# IOTest.net
KiCad netlist of a schematic drawn in Altium Designer
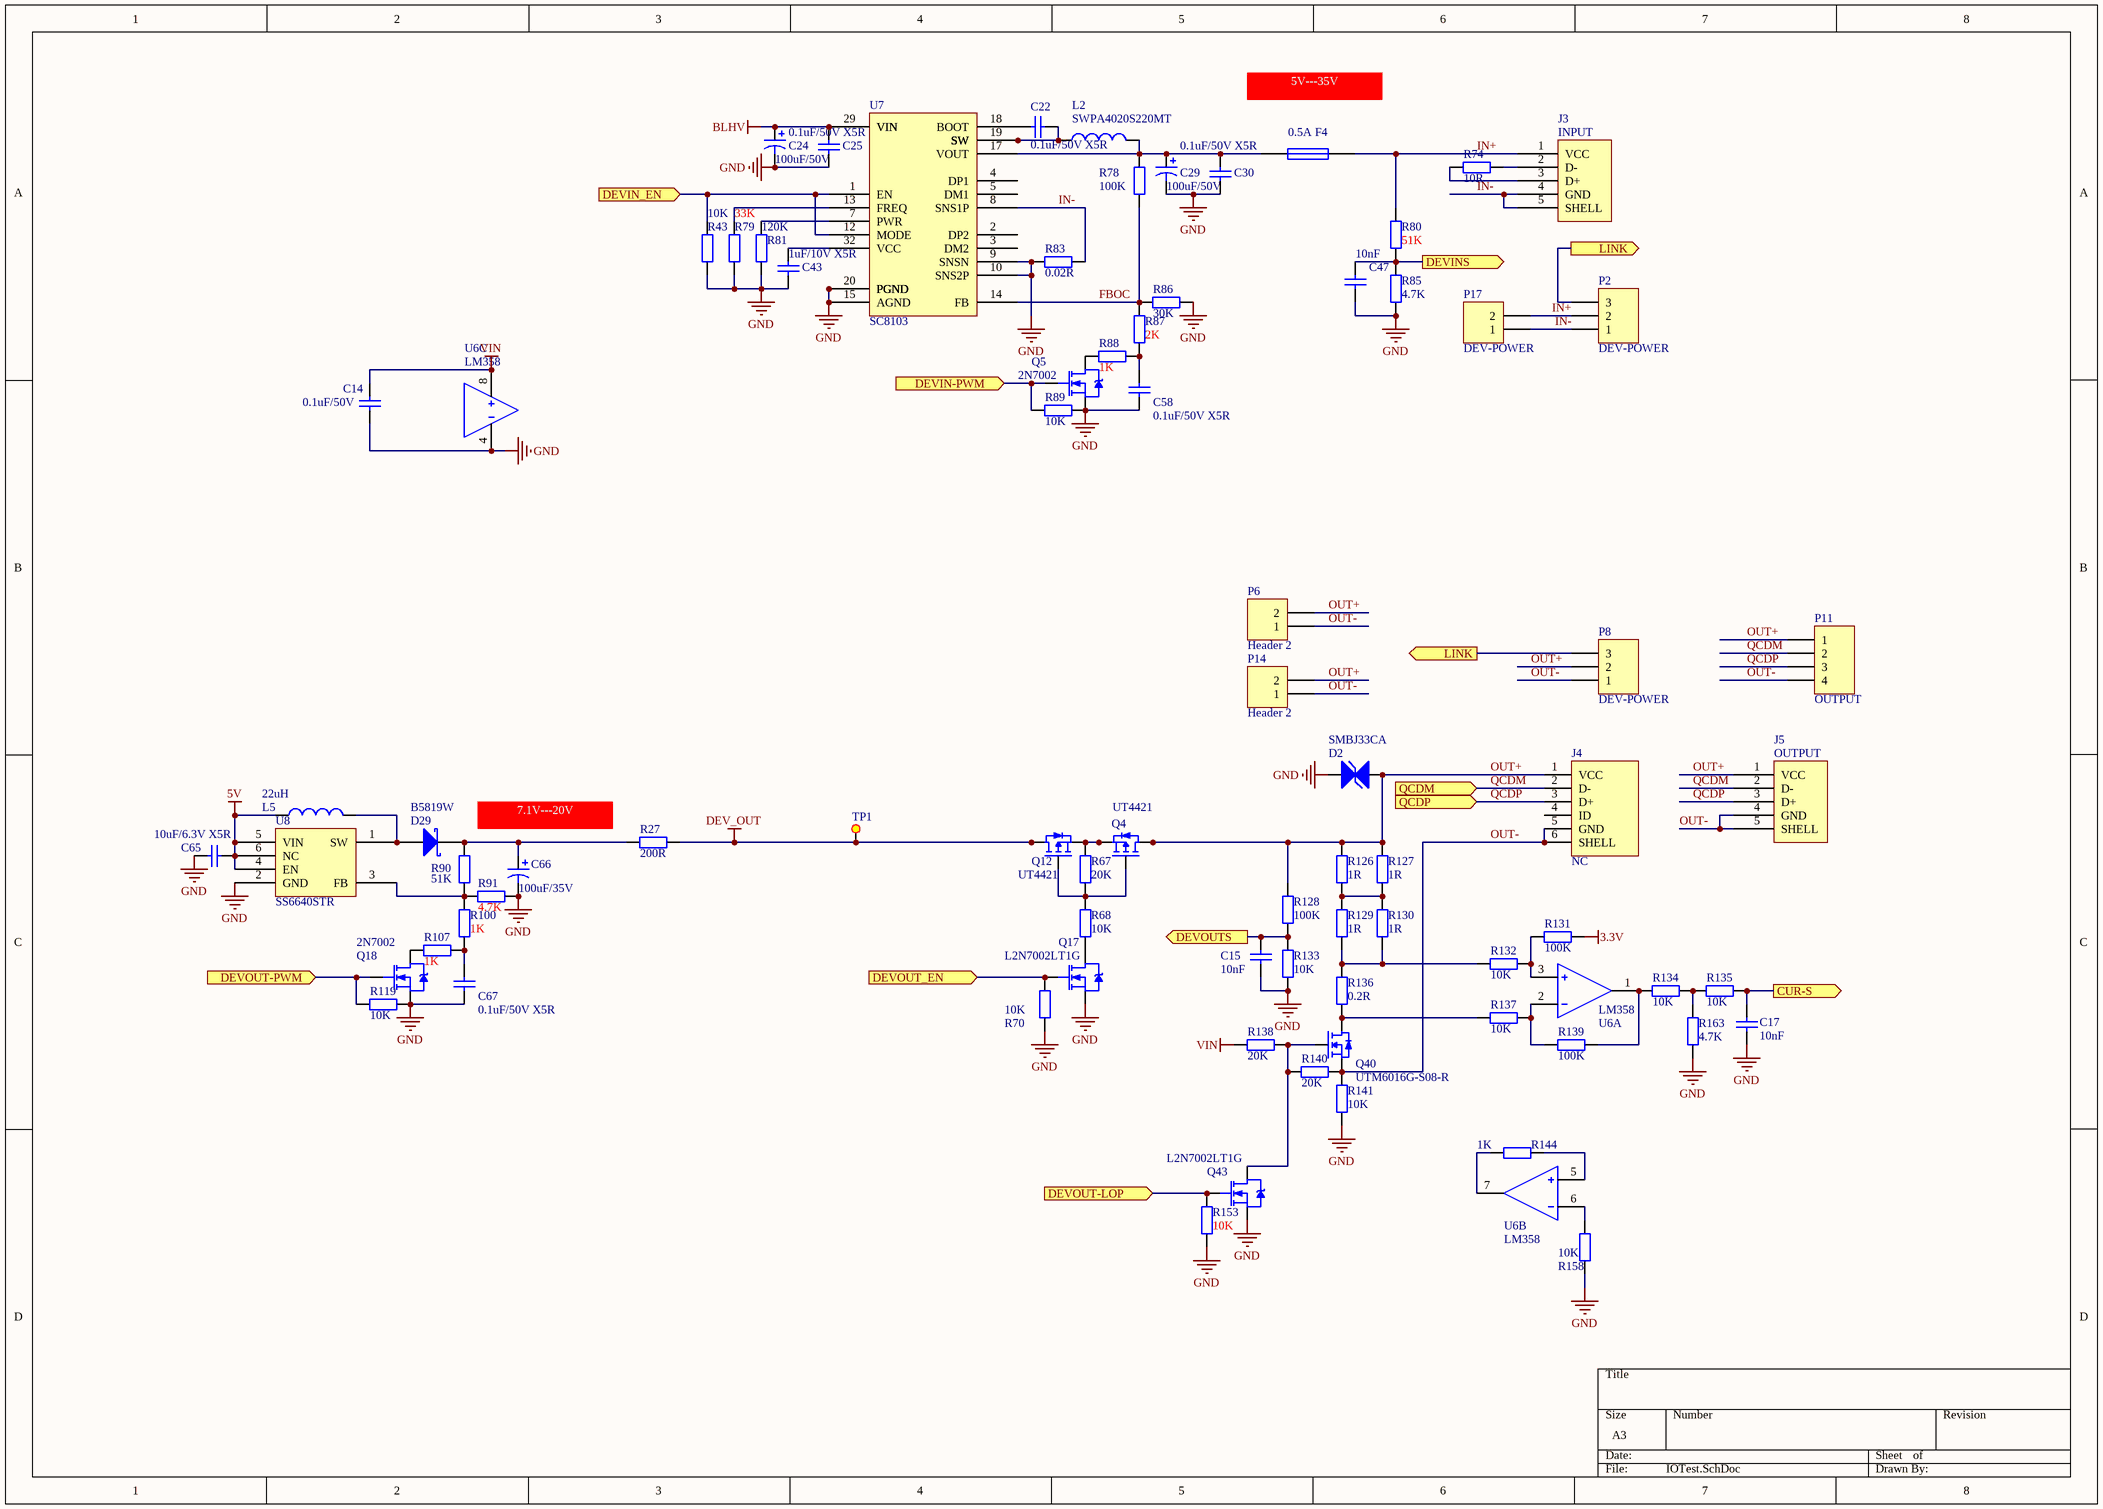
[diagram p0: IOTest.SchDoc]

(export (version "E")
  (design (tool "Eeschema 10.0.6"))
  (components
    (comp (ref "C14")
      (value "0.1uF/50V")
      (footprint "C-0603")
      (description "Capacitor")
      (fields (field (name "PUBLISHER") "Altium Limited"))
      (libsource (lib "Miscellaneous Devices") (part "Cap"))
    )
    (comp (ref "C15")
      (value "10nF")
      (footprint "C-0603")
      (description "Capacitor")
      (fields (field (name "PUBLISHER") "Altium Limited"))
      (libsource (lib "Miscellaneous Devices") (part "Cap"))
    )
    (comp (ref "C17")
      (value "10nF")
      (footprint "C-0603")
      (description "Capacitor")
      (fields (field (name "PUBLISHER") "Altium Limited"))
      (libsource (lib "Miscellaneous Devices") (part "Cap"))
    )
    (comp (ref "C22")
      (value "0.1uF/50V X5R")
      (footprint "C-0603")
      (description "Capacitor")
      (fields (field (name "PUBLISHER") "Altium Limited"))
      (libsource (lib "Miscellaneous Devices") (part "Cap"))
    )
    (comp (ref "C24")
      (value "100uF/50V")
      (footprint "CAPPR-8x12")
      (description "Polarized Capacitor (Radial)")
      (fields (field (name "PUBLISHER") "Altium Limited"))
      (libsource (lib "Miscellaneous Devices") (part "Cap Pol1"))
    )
    (comp (ref "C25")
      (value "0.1uF/50V X5R")
      (footprint "C-0603")
      (description "Capacitor")
      (fields (field (name "PUBLISHER") "Altium Limited"))
      (libsource (lib "Miscellaneous Devices") (part "Cap"))
    )
    (comp (ref "C29")
      (value "100uF/50V")
      (footprint "CAPPR-8x12")
      (description "Polarized Capacitor (Radial)")
      (fields (field (name "PUBLISHER") "Altium Limited"))
      (libsource (lib "Miscellaneous Devices") (part "Cap Pol1"))
    )
    (comp (ref "C30")
      (value "0.1uF/50V X5R")
      (footprint "C-0603")
      (description "Capacitor")
      (fields (field (name "PUBLISHER") "Altium Limited"))
      (libsource (lib "Miscellaneous Devices") (part "Cap"))
    )
    (comp (ref "C43")
      (value "1uF/10V X5R")
      (footprint "C-0603")
      (description "Capacitor")
      (fields (field (name "PUBLISHER") "Altium Limited"))
      (libsource (lib "Miscellaneous Devices") (part "Cap"))
    )
    (comp (ref "C47")
      (value "10nF")
      (footprint "C-0603")
      (description "Capacitor")
      (fields (field (name "PUBLISHER") "Altium Limited"))
      (libsource (lib "Miscellaneous Devices") (part "Cap"))
    )
    (comp (ref "C58")
      (value "0.1uF/50V X5R")
      (footprint "C-0603")
      (description "Capacitor")
      (fields (field (name "PUBLISHER") "Altium Limited"))
      (libsource (lib "Miscellaneous Devices") (part "Cap"))
    )
    (comp (ref "C65")
      (value "10uF/6.3V X5R")
      (footprint "C-0603")
      (description "Capacitor")
      (fields (field (name "PUBLISHER") "Altium Limited"))
      (libsource (lib "Miscellaneous Devices") (part "Cap"))
    )
    (comp (ref "C66")
      (value "100uF/35V")
      (footprint "ToboxStd:CAP-SMD-6.3x7.7")
      (description "Polarized Capacitor (Radial)")
      (fields (field (name "PUBLISHER") "Altium Limited"))
      (libsource (lib "Miscellaneous Devices") (part "Cap Pol1"))
    )
    (comp (ref "C67")
      (value "0.1uF/50V X5R")
      (footprint "C-0603")
      (description "Capacitor")
      (fields (field (name "PUBLISHER") "Altium Limited"))
      (libsource (lib "Miscellaneous Devices") (part "Cap"))
    )
    (comp (ref "D2") (value "SMBJ33CA") (footprint "SMBJ") (libsource (lib "ToboxStd") (part "TVS-D")))
    (comp (ref "D29")
      (value "B5819W")
      (footprint "SOD-123FL")
      (description "Schottky Diode")
      (fields (field (name "PUBLISHER") "Altium Limited"))
      (libsource (lib "Miscellaneous Devices") (part "D Schottky"))
    )
    (comp (ref "F4")
      (value "0.5A")
      (footprint "R-1206")
      (description "Fuse")
      (fields (field (name "PUBLISHER") "Altium Limited"))
      (libsource (lib "Miscellaneous Devices") (part "Fuse 1"))
    )
    (comp (ref "J3")
      (value "INPUT")
      (footprint "ToboxStd:ST-001-15A-1.0")
      (description "USB CONNECTOR")
      (libsource (lib "Tobox") (part "USB-CON"))
    )
    (comp (ref "J4")
      (value "NC")
      (footprint "ST-MICROUSB-03A")
      (description "MICRO-USB-B")
      (libsource (lib "ToboxStd") (part "MICRO-USB-B"))
    )
    (comp (ref "J5")
      (value "OUTPUT")
      (footprint "ToboxStd:ST-001-15A-1.0")
      (description "USB CONNECTOR")
      (libsource (lib "Tobox") (part "USB-CON"))
    )
    (comp (ref "L2")
      (value "SWPA4020S220MT")
      (footprint "SWPA4020S")
      (description "Inductor")
      (fields (field (name "PUBLISHER") "Altium Limited"))
      (libsource (lib "Miscellaneous Devices") (part "Inductor"))
    )
    (comp (ref "L5")
      (value "22uH")
      (footprint "DG3521")
      (description "Inductor")
      (fields (field (name "PUBLISHER") "Altium Limited"))
      (libsource (lib "Miscellaneous Devices") (part "Inductor"))
    )
    (comp (ref "P2")
      (value "DEV-POWER")
      (footprint "XH 2.54-3P")
      (description "Header, 3-Pin")
      (fields (field (name "PUBLISHER") "Altium Limited"))
      (libsource (lib "Miscellaneous Connectors") (part "Header 3"))
    )
    (comp (ref "P6")
      (value "Header 2")
      (footprint "XH 2.54-2P")
      (description "Header, 2-Pin")
      (fields (field (name "PUBLISHER") "Altium Limited"))
      (libsource (lib "Miscellaneous Connectors") (part "Header 2"))
    )
    (comp (ref "P8")
      (value "DEV-POWER")
      (footprint "XH 2.54-3P")
      (description "Header, 3-Pin")
      (fields (field (name "PUBLISHER") "Altium Limited"))
      (libsource (lib "Miscellaneous Connectors") (part "Header 3"))
    )
    (comp (ref "P11")
      (value "OUTPUT")
      (footprint "XH 2.54-4P")
      (description "Header, 4-Pin")
      (fields (field (name "PUBLISHER") "Altium Limited"))
      (libsource (lib "Miscellaneous Connectors") (part "Header 4"))
    )
    (comp (ref "P14")
      (value "Header 2")
      (footprint "XH 2.54-2P")
      (description "Header, 2-Pin")
      (fields (field (name "PUBLISHER") "Altium Limited"))
      (libsource (lib "Miscellaneous Connectors") (part "Header 2"))
    )
    (comp (ref "P17")
      (value "DEV-POWER")
      (footprint "XH 2.54-2P")
      (description "Header, 2-Pin")
      (fields (field (name "PUBLISHER") "Altium Limited"))
      (libsource (lib "Miscellaneous Connectors") (part "Header 2"))
    )
    (comp (ref "Q4")
      (value "UT4421")
      (footprint "SOIC8")
      (description "SO8-PMOS")
      (libsource (lib "Tobox") (part "SO8-PMOS"))
    )
    (comp (ref "Q5")
      (value "2N7002")
      (footprint "SOT23-3")
      (description "N-Channel Power MOSFET")
      (fields (field (name "PUBLISHER") "Altium Limited"))
      (libsource (lib "Miscellaneous Devices") (part "NMOS-2"))
    )
    (comp (ref "Q12")
      (value "UT4421")
      (footprint "SOIC8")
      (description "SO8-PMOS")
      (libsource (lib "Tobox") (part "SO8-PMOS"))
    )
    (comp (ref "Q17")
      (value "L2N7002LT1G")
      (footprint "SOT23-3")
      (description "N-Channel Power MOSFET")
      (fields (field (name "PUBLISHER") "Altium Limited"))
      (libsource (lib "Miscellaneous Devices") (part "NMOS-2"))
    )
    (comp (ref "Q18")
      (value "2N7002")
      (footprint "SOT23-3")
      (description "N-Channel Power MOSFET")
      (fields (field (name "PUBLISHER") "Altium Limited"))
      (libsource (lib "Miscellaneous Devices") (part "NMOS-2"))
    )
    (comp (ref "Q40")
      (value "UTM6016G-S08-R")
      (footprint "SOIC8")
      (description "SO8-NMOS")
      (libsource (lib "Tobox") (part "SO8-NMOS"))
    )
    (comp (ref "Q43")
      (value "L2N7002LT1G")
      (footprint "SOT23-3")
      (description "N-Channel Power MOSFET")
      (fields (field (name "PUBLISHER") "Altium Limited"))
      (libsource (lib "Miscellaneous Devices") (part "NMOS-2"))
    )
    (comp (ref "R27")
      (value "200R")
      (footprint "R-0805")
      (description "Resistor")
      (fields (field (name "PUBLISHER") "Altium Limited"))
      (libsource (lib "Miscellaneous Devices") (part "Res2"))
    )
    (comp (ref "R43")
      (value "10K")
      (footprint "R-0603")
      (description "Resistor")
      (fields (field (name "PUBLISHER") "Altium Limited"))
      (libsource (lib "") (part "Res2_2"))
    )
    (comp (ref "R67")
      (value "20K")
      (footprint "R-0603")
      (description "Resistor")
      (fields (field (name "PUBLISHER") "Altium Limited"))
      (libsource (lib "Miscellaneous Devices") (part "Res2"))
    )
    (comp (ref "R68")
      (value "10K")
      (footprint "R-0603")
      (description "Resistor")
      (fields (field (name "PUBLISHER") "Altium Limited"))
      (libsource (lib "Miscellaneous Devices") (part "Res2"))
    )
    (comp (ref "R70")
      (value "10K")
      (footprint "R-0603")
      (description "Resistor")
      (fields (field (name "PUBLISHER") "Altium Limited"))
      (libsource (lib "") (part "Res2_2"))
    )
    (comp (ref "R74")
      (value "10R")
      (footprint "R-0603")
      (description "Resistor")
      (fields (field (name "PUBLISHER") "Altium Limited"))
      (libsource (lib "") (part "Res2_3"))
    )
    (comp (ref "R78")
      (value "100K")
      (footprint "R-0603")
      (description "Resistor")
      (fields (field (name "PUBLISHER") "Altium Limited"))
      (libsource (lib "") (part "Res2_3"))
    )
    (comp (ref "R79")
      (value "33K")
      (footprint "R-0603")
      (description "Resistor")
      (fields (field (name "PUBLISHER") "Altium Limited"))
      (libsource (lib "") (part "Res2_2"))
    )
    (comp (ref "R80")
      (value "51K")
      (footprint "R-0603")
      (description "Resistor")
      (fields (field (name "PUBLISHER") "Altium Limited"))
      (libsource (lib "Miscellaneous Devices") (part "Res2"))
    )
    (comp (ref "R81")
      (value "120K")
      (footprint "R-0603")
      (description "Resistor")
      (fields (field (name "PUBLISHER") "Altium Limited"))
      (libsource (lib "") (part "Res2_2"))
    )
    (comp (ref "R83")
      (value "0.02R")
      (footprint "R-2010")
      (description "Resistor")
      (fields (field (name "PUBLISHER") "Altium Limited"))
      (libsource (lib "Miscellaneous Devices") (part "Res2"))
    )
    (comp (ref "R85")
      (value "4.7K")
      (footprint "R-0603")
      (description "Resistor")
      (fields (field (name "PUBLISHER") "Altium Limited"))
      (libsource (lib "Miscellaneous Devices") (part "Res2"))
    )
    (comp (ref "R86")
      (value "30K")
      (footprint "R-0603")
      (description "Resistor")
      (fields (field (name "PUBLISHER") "Altium Limited"))
      (libsource (lib "") (part "Res2_1"))
    )
    (comp (ref "R87")
      (value "2K")
      (footprint "R-0603")
      (description "Resistor")
      (fields (field (name "PUBLISHER") "Altium Limited"))
      (libsource (lib "") (part "Res2_2"))
    )
    (comp (ref "R88")
      (value "1K")
      (footprint "R-0603")
      (description "Resistor")
      (fields (field (name "PUBLISHER") "Altium Limited"))
      (libsource (lib "") (part "Res2_1"))
    )
    (comp (ref "R89")
      (value "10K")
      (footprint "R-0603")
      (description "Resistor")
      (fields (field (name "PUBLISHER") "Altium Limited"))
      (libsource (lib "") (part "Res2_1"))
    )
    (comp (ref "R90")
      (value "51K")
      (footprint "R-0603")
      (description "Resistor")
      (fields (field (name "PUBLISHER") "Altium Limited"))
      (libsource (lib "") (part "Res2_1"))
    )
    (comp (ref "R91")
      (value "4.7K")
      (footprint "R-0603")
      (description "Resistor")
      (fields (field (name "PUBLISHER") "Altium Limited"))
      (libsource (lib "") (part "Res2_2"))
    )
    (comp (ref "R100")
      (value "1K")
      (footprint "R-0603")
      (description "Resistor")
      (fields (field (name "PUBLISHER") "Altium Limited"))
      (libsource (lib "") (part "Res2_2"))
    )
    (comp (ref "R107")
      (value "1K")
      (footprint "R-0603")
      (description "Resistor")
      (fields (field (name "PUBLISHER") "Altium Limited"))
      (libsource (lib "") (part "Res2_1"))
    )
    (comp (ref "R119")
      (value "10K")
      (footprint "R-0603")
      (description "Resistor")
      (fields (field (name "PUBLISHER") "Altium Limited"))
      (libsource (lib "") (part "Res2_1"))
    )
    (comp (ref "R126")
      (value "1R")
      (footprint "ToboxStd:R-2512")
      (description "Resistor")
      (fields (field (name "PUBLISHER") "Altium Limited"))
      (libsource (lib "") (part "Res2_1"))
    )
    (comp (ref "R127")
      (value "1R")
      (footprint "ToboxStd:R-2512")
      (description "Resistor")
      (fields (field (name "PUBLISHER") "Altium Limited"))
      (libsource (lib "") (part "Res2_2"))
    )
    (comp (ref "R128")
      (value "100K")
      (footprint "R-0603")
      (description "Resistor")
      (fields (field (name "PUBLISHER") "Altium Limited"))
      (libsource (lib "") (part "Res2_2"))
    )
    (comp (ref "R129")
      (value "1R")
      (footprint "ToboxStd:R-2512")
      (description "Resistor")
      (fields (field (name "PUBLISHER") "Altium Limited"))
      (libsource (lib "") (part "Res2_2"))
    )
    (comp (ref "R130")
      (value "1R")
      (footprint "ToboxStd:R-2512")
      (description "Resistor")
      (fields (field (name "PUBLISHER") "Altium Limited"))
      (libsource (lib "") (part "Res2_3"))
    )
    (comp (ref "R131")
      (value "100K")
      (footprint "R-0603")
      (description "Resistor")
      (fields (field (name "PUBLISHER") "Altium Limited"))
      (libsource (lib "Miscellaneous Devices") (part "Res2"))
    )
    (comp (ref "R132")
      (value "10K")
      (footprint "R-0603")
      (description "Resistor")
      (fields (field (name "PUBLISHER") "Altium Limited"))
      (libsource (lib "Miscellaneous Devices") (part "Res2"))
    )
    (comp (ref "R133")
      (value "10K")
      (footprint "R-0603")
      (description "Resistor")
      (fields (field (name "PUBLISHER") "Altium Limited"))
      (libsource (lib "") (part "Res2_2"))
    )
    (comp (ref "R134")
      (value "10K")
      (footprint "R-0603")
      (description "Resistor")
      (fields (field (name "PUBLISHER") "Altium Limited"))
      (libsource (lib "Miscellaneous Devices") (part "Res2"))
    )
    (comp (ref "R135")
      (value "10K")
      (footprint "R-0603")
      (description "Resistor")
      (fields (field (name "PUBLISHER") "Altium Limited"))
      (libsource (lib "Miscellaneous Devices") (part "Res2"))
    )
    (comp (ref "R136")
      (value "0.2R")
      (footprint "R-2512HP")
      (description "Resistor")
      (fields (field (name "PUBLISHER") "Altium Limited"))
      (libsource (lib "") (part "Res2_2"))
    )
    (comp (ref "R137")
      (value "10K")
      (footprint "R-0603")
      (description "Resistor")
      (fields (field (name "PUBLISHER") "Altium Limited"))
      (libsource (lib "Miscellaneous Devices") (part "Res2"))
    )
    (comp (ref "R138")
      (value "20K")
      (footprint "R-0603")
      (description "Resistor")
      (fields (field (name "PUBLISHER") "Altium Limited"))
      (libsource (lib "Miscellaneous Devices") (part "Res2"))
    )
    (comp (ref "R139")
      (value "100K")
      (footprint "R-0603")
      (description "Resistor")
      (fields (field (name "PUBLISHER") "Altium Limited"))
      (libsource (lib "Miscellaneous Devices") (part "Res2"))
    )
    (comp (ref "R140")
      (value "20K")
      (footprint "R-0603")
      (description "Resistor")
      (fields (field (name "PUBLISHER") "Altium Limited"))
      (libsource (lib "Miscellaneous Devices") (part "Res2"))
    )
    (comp (ref "R141")
      (value "10K")
      (footprint "R-0603")
      (description "Resistor")
      (fields (field (name "PUBLISHER") "Altium Limited"))
      (libsource (lib "") (part "Res2_3"))
    )
    (comp (ref "R144")
      (value "1K")
      (footprint "R-0603")
      (description "Resistor")
      (fields (field (name "PUBLISHER") "Altium Limited"))
      (libsource (lib "") (part "Res2_3"))
    )
    (comp (ref "R153")
      (value "10K")
      (footprint "R-0603")
      (description "Resistor")
      (fields (field (name "PUBLISHER") "Altium Limited"))
      (libsource (lib "") (part "Res2_3"))
    )
    (comp (ref "R158")
      (value "10K")
      (footprint "R-0603")
      (description "Resistor")
      (fields (field (name "PUBLISHER") "Altium Limited"))
      (libsource (lib "") (part "Res2_1"))
    )
    (comp (ref "R163")
      (value "4.7K")
      (footprint "R-0603")
      (description "Resistor")
      (fields (field (name "PUBLISHER") "Altium Limited"))
      (libsource (lib "") (part "Res2_2"))
    )
    (comp (ref "TP1") (value "~") (footprint "TestPoint-1.5mm") (libsource (lib "Tobox") (part "TEST_P")))
    (comp (ref "U6") (value "LM358") (footprint "SOIC8") (libsource (lib "Tobox") (part "Dual_OPAMP")))
    (comp (ref "U7") (value "SC8103") (footprint "SC8103") (libsource (lib "ToboxStd") (part "SC8103")))
    (comp (ref "U8")
      (value "SS6640STR")
      (footprint "SOT23-6")
      (description "AX5523")
      (libsource (lib "ToboxStd") (part "AX5523"))
    )
  )
  (nets
    (net (code "1") (name "/CUR-S") (class "Default")
      (node (ref "C17") (pin "2") (pinfunction "2_2") (pintype "passive"))
      (node (ref "R135") (pin "2") (pinfunction "2_2") (pintype "passive"))
    )
    (net (code "2") (name "/DEVIN-PWM") (class "Default")
      (node (ref "Q5") (pin "1") (pinfunction "G_1") (pintype "passive"))
      (node (ref "R89") (pin "2") (pinfunction "2_2") (pintype "passive"))
    )
    (net (code "3") (name "/DEVINS") (class "Default")
      (node (ref "C47") (pin "2") (pinfunction "2_2") (pintype "passive"))
      (node (ref "R80") (pin "1") (pinfunction "1_1") (pintype "passive"))
      (node (ref "R85") (pin "2") (pinfunction "2_2") (pintype "passive"))
    )
    (net (code "4") (name "/DEVIN_EN") (class "Default")
      (node (ref "R43") (pin "2") (pinfunction "2_2") (pintype "passive"))
      (node (ref "U7") (pin "1") (pinfunction "EN_1") (pintype "passive"))
      (node (ref "U7") (pin "12") (pinfunction "MODE_12") (pintype "passive"))
    )
    (net (code "5") (name "/DEVOUT-LOP") (class "Default")
      (node (ref "Q43") (pin "1") (pinfunction "G_1") (pintype "passive"))
      (node (ref "R153") (pin "1") (pinfunction "1_1") (pintype "passive"))
    )
    (net (code "6") (name "/DEVOUT-PWM") (class "Default")
      (node (ref "Q18") (pin "1") (pinfunction "G_1") (pintype "passive"))
      (node (ref "R119") (pin "2") (pinfunction "2_2") (pintype "passive"))
    )
    (net (code "7") (name "/DEVOUTS") (class "Default")
      (node (ref "C15") (pin "2") (pinfunction "2_2") (pintype "passive"))
      (node (ref "R128") (pin "1") (pinfunction "1_1") (pintype "passive"))
      (node (ref "R133") (pin "2") (pinfunction "2_2") (pintype "passive"))
    )
    (net (code "8") (name "/DEVOUT_EN") (class "Default")
      (node (ref "Q17") (pin "1") (pinfunction "G_1") (pintype "passive"))
      (node (ref "R70") (pin "2") (pinfunction "2_2") (pintype "passive"))
    )
    (net (code "9") (name "/FBOC") (class "Default")
      (node (ref "R78") (pin "2") (pinfunction "2_2") (pintype "passive"))
      (node (ref "R86") (pin "2") (pinfunction "2_2") (pintype "passive"))
      (node (ref "R87") (pin "2") (pinfunction "2_2") (pintype "passive"))
      (node (ref "U7") (pin "14") (pinfunction "FB_14") (pintype "passive"))
    )
    (net (code "10") (name "/IN+") (class "Default")
      (node (ref "F4") (pin "2") (pinfunction "2_2") (pintype "passive"))
      (node (ref "J3") (pin "1") (pinfunction "VCC_1") (pintype "passive"))
      (node (ref "P17") (pin "2") (pinfunction "2_2") (pintype "passive"))
      (node (ref "P2") (pin "2") (pinfunction "2_2") (pintype "passive"))
      (node (ref "R80") (pin "2") (pinfunction "2_2") (pintype "passive"))
    )
    (net (code "11") (name "/IN-") (class "Default")
      (node (ref "J3") (pin "4") (pinfunction "GND_4") (pintype "passive"))
      (node (ref "J3") (pin "5") (pinfunction "SHELL_5") (pintype "passive"))
      (node (ref "P17") (pin "1") (pinfunction "1_1") (pintype "passive"))
      (node (ref "P2") (pin "1") (pinfunction "1_1") (pintype "passive"))
      (node (ref "R83") (pin "2") (pinfunction "2_2") (pintype "passive"))
      (node (ref "U7") (pin "8") (pinfunction "SNS1P_8") (pintype "passive"))
    )
    (net (code "12") (name "/LINK") (class "Default")
      (node (ref "P2") (pin "3") (pinfunction "3_3") (pintype "passive"))
      (node (ref "P8") (pin "3") (pinfunction "3_3") (pintype "passive"))
    )
    (net (code "13") (name "/OUT+") (class "Default")
      (node (ref "D2") (pin "2") (pinfunction "2_2") (pintype "passive"))
      (node (ref "J4") (pin "1") (pinfunction "VCC_1") (pintype "passive"))
      (node (ref "J5") (pin "1") (pinfunction "VCC_1") (pintype "passive"))
      (node (ref "P11") (pin "1") (pinfunction "1_1") (pintype "passive"))
      (node (ref "P14") (pin "2") (pinfunction "2_2") (pintype "passive"))
      (node (ref "P6") (pin "2") (pinfunction "2_2") (pintype "passive"))
      (node (ref "P8") (pin "2") (pinfunction "2_2") (pintype "passive"))
      (node (ref "Q4") (pin "5") (pinfunction "D_5") (pintype "passive"))
      (node (ref "Q4") (pin "6") (pinfunction "D_6") (pintype "passive"))
      (node (ref "Q4") (pin "7") (pinfunction "D_7") (pintype "passive"))
      (node (ref "Q4") (pin "8") (pinfunction "D_8") (pintype "passive"))
      (node (ref "R126") (pin "1") (pinfunction "1_1") (pintype "passive"))
      (node (ref "R127") (pin "2") (pinfunction "2_2") (pintype "passive"))
      (node (ref "R128") (pin "2") (pinfunction "2_2") (pintype "passive"))
    )
    (net (code "14") (name "/OUT-") (class "Default")
      (node (ref "J4") (pin "5") (pinfunction "GND_5") (pintype "passive"))
      (node (ref "J4") (pin "6") (pinfunction "SHELL_6") (pintype "passive"))
      (node (ref "J5") (pin "4") (pinfunction "GND_4") (pintype "passive"))
      (node (ref "J5") (pin "5") (pinfunction "SHELL_5") (pintype "passive"))
      (node (ref "P11") (pin "4") (pinfunction "4_4") (pintype "passive"))
      (node (ref "P14") (pin "1") (pinfunction "1_1") (pintype "passive"))
      (node (ref "P6") (pin "1") (pinfunction "1_1") (pintype "passive"))
      (node (ref "P8") (pin "1") (pinfunction "1_1") (pintype "passive"))
      (node (ref "Q40") (pin "1") (pinfunction "S_1") (pintype "passive"))
      (node (ref "Q40") (pin "2") (pinfunction "S_2") (pintype "passive"))
      (node (ref "Q40") (pin "3") (pinfunction "S_3") (pintype "passive"))
      (node (ref "R140") (pin "2") (pinfunction "2_2") (pintype "passive"))
      (node (ref "R141") (pin "1") (pinfunction "1_1") (pintype "passive"))
    )
    (net (code "15") (name "/QCDM") (class "Default")
      (node (ref "J4") (pin "2") (pinfunction "D-_2") (pintype "passive"))
      (node (ref "J5") (pin "2") (pinfunction "D-_2") (pintype "passive"))
      (node (ref "P11") (pin "2") (pinfunction "2_2") (pintype "passive"))
    )
    (net (code "16") (name "/QCDP") (class "Default")
      (node (ref "J4") (pin "3") (pinfunction "D+_3") (pintype "passive"))
      (node (ref "J5") (pin "3") (pinfunction "D+_3") (pintype "passive"))
      (node (ref "P11") (pin "3") (pinfunction "3_3") (pintype "passive"))
    )
    (net (code "17") (name "3.3V") (class "Default")
      (node (ref "R131") (pin "2") (pinfunction "2_2") (pintype "passive"))
    )
    (net (code "18") (name "5V") (class "Default")
      (node (ref "C65") (pin "2") (pinfunction "2_2") (pintype "passive"))
      (node (ref "L5") (pin "1") (pinfunction "1_1") (pintype "passive"))
      (node (ref "U8") (pin "4") (pinfunction "EN_4") (pintype "passive"))
      (node (ref "U8") (pin "5") (pinfunction "VIN_5") (pintype "passive"))
      (node (ref "U8") (pin "6") (pinfunction "NC_6") (pintype "passive"))
    )
    (net (code "19") (name "BLHV") (class "Default")
      (node (ref "C24") (pin "1") (pinfunction "1_1") (pintype "passive"))
      (node (ref "C25") (pin "2") (pinfunction "2_2") (pintype "passive"))
      (node (ref "U7") (pin "29") (pinfunction "VIN_29") (pintype "passive"))
      (node (ref "U7") (pin "30") (pinfunction "VIN_30") (pintype "passive"))
      (node (ref "U7") (pin "31") (pinfunction "VIN_31") (pintype "passive"))
    )
    (net (code "20") (name "DEV_OUT") (class "Default")
      (node (ref "Q12") (pin "5") (pinfunction "D_5") (pintype "passive"))
      (node (ref "Q12") (pin "6") (pinfunction "D_6") (pintype "passive"))
      (node (ref "Q12") (pin "7") (pinfunction "D_7") (pintype "passive"))
      (node (ref "Q12") (pin "8") (pinfunction "D_8") (pintype "passive"))
      (node (ref "R27") (pin "2") (pinfunction "2_2") (pintype "passive"))
      (node (ref "TP1") (pin "1") (pinfunction "1_1") (pintype "passive"))
    )
    (net (code "21") (name "GND") (class "Default")
      (node (ref "C14") (pin "2") (pinfunction "2_2") (pintype "passive"))
      (node (ref "C15") (pin "1") (pinfunction "1_1") (pintype "passive"))
      (node (ref "C17") (pin "1") (pinfunction "1_1") (pintype "passive"))
      (node (ref "C24") (pin "2") (pinfunction "2_2") (pintype "passive"))
      (node (ref "C25") (pin "1") (pinfunction "1_1") (pintype "passive"))
      (node (ref "C29") (pin "2") (pinfunction "2_2") (pintype "passive"))
      (node (ref "C30") (pin "1") (pinfunction "1_1") (pintype "passive"))
      (node (ref "C43") (pin "1") (pinfunction "1_1") (pintype "passive"))
      (node (ref "C47") (pin "1") (pinfunction "1_1") (pintype "passive"))
      (node (ref "C58") (pin "2") (pinfunction "2_2") (pintype "passive"))
      (node (ref "C65") (pin "1") (pinfunction "1_1") (pintype "passive"))
      (node (ref "C66") (pin "2") (pinfunction "2_2") (pintype "passive"))
      (node (ref "C67") (pin "2") (pinfunction "2_2") (pintype "passive"))
      (node (ref "D2") (pin "1") (pinfunction "1_1") (pintype "passive"))
      (node (ref "Q17") (pin "2") (pinfunction "D_2") (pintype "passive"))
      (node (ref "Q18") (pin "2") (pinfunction "D_2") (pintype "passive"))
      (node (ref "Q43") (pin "2") (pinfunction "D_2") (pintype "passive"))
      (node (ref "Q5") (pin "2") (pinfunction "D_2") (pintype "passive"))
      (node (ref "R119") (pin "1") (pinfunction "1_1") (pintype "passive"))
      (node (ref "R133") (pin "1") (pinfunction "1_1") (pintype "passive"))
      (node (ref "R141") (pin "2") (pinfunction "2_2") (pintype "passive"))
      (node (ref "R153") (pin "2") (pinfunction "2_2") (pintype "passive"))
      (node (ref "R158") (pin "2") (pinfunction "2_2") (pintype "passive"))
      (node (ref "R163") (pin "1") (pinfunction "1_1") (pintype "passive"))
      (node (ref "R43") (pin "1") (pinfunction "1_1") (pintype "passive"))
      (node (ref "R70") (pin "1") (pinfunction "1_1") (pintype "passive"))
      (node (ref "R79") (pin "1") (pinfunction "1_1") (pintype "passive"))
      (node (ref "R81") (pin "1") (pinfunction "1_1") (pintype "passive"))
      (node (ref "R83") (pin "1") (pinfunction "1_1") (pintype "passive"))
      (node (ref "R85") (pin "1") (pinfunction "1_1") (pintype "passive"))
      (node (ref "R86") (pin "1") (pinfunction "1_1") (pintype "passive"))
      (node (ref "R89") (pin "1") (pinfunction "1_1") (pintype "passive"))
      (node (ref "R91") (pin "2") (pinfunction "2_2") (pintype "passive"))
      (node (ref "U6") (pin "4") (pinfunction "4_4") (pintype "passive"))
      (node (ref "U7") (pin "10") (pinfunction "SNS2P_10") (pintype "passive"))
      (node (ref "U7") (pin "15") (pinfunction "AGND_15") (pintype "passive"))
      (node (ref "U7") (pin "20") (pinfunction "PGND_20") (pintype "passive"))
      (node (ref "U7") (pin "21") (pinfunction "PGND_21") (pintype "passive"))
      (node (ref "U7") (pin "22") (pinfunction "PGND_22") (pintype "passive"))
      (node (ref "U7") (pin "23") (pinfunction "PGND_23") (pintype "passive"))
      (node (ref "U7") (pin "24") (pinfunction "PGND_24") (pintype "passive"))
      (node (ref "U7") (pin "9") (pinfunction "SNSN_9") (pintype "passive"))
      (node (ref "U8") (pin "2") (pinfunction "GND_2") (pintype "passive"))
    )
    (net (code "22") (name "Net-(C22-Pad1)") (class "Default")
      (node (ref "C22") (pin "1") (pinfunction "1_1") (pintype "passive"))
      (node (ref "L2") (pin "1") (pinfunction "1_1") (pintype "passive"))
      (node (ref "U7") (pin "16") (pinfunction "SW_16") (pintype "passive"))
      (node (ref "U7") (pin "19") (pinfunction "SW_19") (pintype "passive"))
      (node (ref "U7") (pin "25") (pinfunction "SW_25") (pintype "passive"))
      (node (ref "U7") (pin "26") (pinfunction "SW_26") (pintype "passive"))
      (node (ref "U7") (pin "27") (pinfunction "SW_27") (pintype "passive"))
      (node (ref "U7") (pin "28") (pinfunction "SW_28") (pintype "passive"))
    )
    (net (code "23") (name "Net-(C58-Pad1)") (class "Default")
      (node (ref "C58") (pin "1") (pinfunction "1_1") (pintype "passive"))
      (node (ref "R87") (pin "1") (pinfunction "1_1") (pintype "passive"))
      (node (ref "R88") (pin "1") (pinfunction "1_1") (pintype "passive"))
    )
    (net (code "24") (name "Net-(C67-Pad1)") (class "Default")
      (node (ref "C67") (pin "1") (pinfunction "1_1") (pintype "passive"))
      (node (ref "R100") (pin "1") (pinfunction "1_1") (pintype "passive"))
      (node (ref "R107") (pin "1") (pinfunction "1_1") (pintype "passive"))
    )
    (net (code "25") (name "Net-(D29-A)") (class "Default")
      (node (ref "D29") (pin "1") (pinfunction "A_1") (pintype "passive"))
      (node (ref "L5") (pin "2") (pinfunction "2_2") (pintype "passive"))
      (node (ref "U8") (pin "1") (pinfunction "SW_1") (pintype "passive"))
    )
    (net (code "26") (name "Net-(D29-K)") (class "Default")
      (node (ref "C66") (pin "1") (pinfunction "1_1") (pintype "passive"))
      (node (ref "D29") (pin "2") (pinfunction "K_2") (pintype "passive"))
      (node (ref "R27") (pin "1") (pinfunction "1_1") (pintype "passive"))
      (node (ref "R90") (pin "1") (pinfunction "1_1") (pintype "passive"))
    )
    (net (code "27") (name "Net-(J3-D+)") (class "Default")
      (node (ref "J3") (pin "3") (pinfunction "D+_3") (pintype "passive"))
      (node (ref "R74") (pin "2") (pinfunction "2_2") (pintype "passive"))
    )
    (net (code "28") (name "Net-(J3-D-)") (class "Default")
      (node (ref "J3") (pin "2") (pinfunction "D-_2") (pintype "passive"))
      (node (ref "R74") (pin "1") (pinfunction "1_1") (pintype "passive"))
    )
    (net (code "29") (name "Net-(Q5-S)") (class "Default")
      (node (ref "Q5") (pin "3") (pinfunction "S_3") (pintype "passive"))
      (node (ref "R88") (pin "2") (pinfunction "2_2") (pintype "passive"))
    )
    (net (code "30") (name "Net-(Q12-G)") (class "Default")
      (node (ref "Q12") (pin "4") (pinfunction "G_4") (pintype "passive"))
      (node (ref "Q4") (pin "4") (pinfunction "G_4") (pintype "passive"))
      (node (ref "R67") (pin "1") (pinfunction "1_1") (pintype "passive"))
      (node (ref "R68") (pin "2") (pinfunction "2_2") (pintype "passive"))
    )
    (net (code "31") (name "Net-(Q12-S-Pad1)") (class "Default")
      (node (ref "Q12") (pin "1") (pinfunction "S_1") (pintype "passive"))
      (node (ref "Q12") (pin "2") (pinfunction "S_2") (pintype "passive"))
      (node (ref "Q12") (pin "3") (pinfunction "S_3") (pintype "passive"))
      (node (ref "Q4") (pin "1") (pinfunction "S_1") (pintype "passive"))
      (node (ref "Q4") (pin "2") (pinfunction "S_2") (pintype "passive"))
      (node (ref "Q4") (pin "3") (pinfunction "S_3") (pintype "passive"))
      (node (ref "R67") (pin "2") (pinfunction "2_2") (pintype "passive"))
    )
    (net (code "32") (name "Net-(Q17-S)") (class "Default")
      (node (ref "Q17") (pin "3") (pinfunction "S_3") (pintype "passive"))
      (node (ref "R68") (pin "1") (pinfunction "1_1") (pintype "passive"))
    )
    (net (code "33") (name "Net-(Q18-S)") (class "Default")
      (node (ref "Q18") (pin "3") (pinfunction "S_3") (pintype "passive"))
      (node (ref "R107") (pin "2") (pinfunction "2_2") (pintype "passive"))
    )
    (net (code "34") (name "Net-(Q40-D-Pad5)") (class "Default")
      (node (ref "Q40") (pin "5") (pinfunction "D_5") (pintype "passive"))
      (node (ref "Q40") (pin "6") (pinfunction "D_6") (pintype "passive"))
      (node (ref "Q40") (pin "7") (pinfunction "D_7") (pintype "passive"))
      (node (ref "Q40") (pin "8") (pinfunction "D_8") (pintype "passive"))
      (node (ref "R136") (pin "1") (pinfunction "1_1") (pintype "passive"))
      (node (ref "R137") (pin "1") (pinfunction "1_1") (pintype "passive"))
    )
    (net (code "35") (name "Net-(Q40-G)") (class "Default")
      (node (ref "Q40") (pin "4") (pinfunction "G_4") (pintype "passive"))
      (node (ref "Q43") (pin "3") (pinfunction "S_3") (pintype "passive"))
      (node (ref "R138") (pin "2") (pinfunction "2_2") (pintype "passive"))
      (node (ref "R140") (pin "1") (pinfunction "1_1") (pintype "passive"))
    )
    (net (code "36") (name "Net-(R126-Pad2)") (class "Default")
      (node (ref "R126") (pin "2") (pinfunction "2_2") (pintype "passive"))
      (node (ref "R127") (pin "1") (pinfunction "1_1") (pintype "passive"))
      (node (ref "R129") (pin "2") (pinfunction "2_2") (pintype "passive"))
      (node (ref "R130") (pin "1") (pinfunction "1_1") (pintype "passive"))
    )
    (net (code "37") (name "Net-(R129-Pad1)") (class "Default")
      (node (ref "R129") (pin "1") (pinfunction "1_1") (pintype "passive"))
      (node (ref "R130") (pin "2") (pinfunction "2_2") (pintype "passive"))
      (node (ref "R132") (pin "1") (pinfunction "1_1") (pintype "passive"))
      (node (ref "R136") (pin "2") (pinfunction "2_2") (pintype "passive"))
    )
    (net (code "38") (name "Net-(R131-Pad1)") (class "Default")
      (node (ref "R131") (pin "1") (pinfunction "1_1") (pintype "passive"))
      (node (ref "R132") (pin "2") (pinfunction "2_2") (pintype "passive"))
      (node (ref "U6") (pin "3") (pinfunction "3_3") (pintype "passive"))
    )
    (net (code "39") (name "Net-(R134-Pad1)") (class "Default")
      (node (ref "R134") (pin "1") (pinfunction "1_1") (pintype "passive"))
      (node (ref "R139") (pin "2") (pinfunction "2_2") (pintype "passive"))
      (node (ref "U6") (pin "1") (pinfunction "1_1") (pintype "passive"))
    )
    (net (code "40") (name "Net-(R134-Pad2)") (class "Default")
      (node (ref "R134") (pin "2") (pinfunction "2_2") (pintype "passive"))
      (node (ref "R135") (pin "1") (pinfunction "1_1") (pintype "passive"))
      (node (ref "R163") (pin "2") (pinfunction "2_2") (pintype "passive"))
    )
    (net (code "41") (name "Net-(R137-Pad2)") (class "Default")
      (node (ref "R137") (pin "2") (pinfunction "2_2") (pintype "passive"))
      (node (ref "R139") (pin "1") (pinfunction "1_1") (pintype "passive"))
      (node (ref "U6") (pin "2") (pinfunction "2_2") (pintype "passive"))
    )
    (net (code "42") (name "Net-(R144-Pad1)") (class "Default")
      (node (ref "R144") (pin "1") (pinfunction "1_1") (pintype "passive"))
      (node (ref "U6") (pin "5") (pinfunction "5_5") (pintype "passive"))
    )
    (net (code "43") (name "Net-(R144-Pad2)") (class "Default")
      (node (ref "R144") (pin "2") (pinfunction "2_2") (pintype "passive"))
      (node (ref "U6") (pin "7") (pinfunction "7_7") (pintype "passive"))
    )
    (net (code "44") (name "Net-(R158-Pad1)") (class "Default")
      (node (ref "R158") (pin "1") (pinfunction "1_1") (pintype "passive"))
      (node (ref "U6") (pin "6") (pinfunction "6_6") (pintype "passive"))
    )
    (net (code "45") (name "Net-(U7-BOOT)") (class "Default")
      (node (ref "C22") (pin "2") (pinfunction "2_2") (pintype "passive"))
      (node (ref "U7") (pin "18") (pinfunction "BOOT_18") (pintype "passive"))
    )
    (net (code "46") (name "Net-(U7-FREQ)") (class "Default")
      (node (ref "R79") (pin "2") (pinfunction "2_2") (pintype "passive"))
      (node (ref "U7") (pin "13") (pinfunction "FREQ_13") (pintype "passive"))
    )
    (net (code "47") (name "Net-(U7-PWR)") (class "Default")
      (node (ref "R81") (pin "2") (pinfunction "2_2") (pintype "passive"))
      (node (ref "U7") (pin "7") (pinfunction "PWR_7") (pintype "passive"))
    )
    (net (code "48") (name "Net-(U7-VCC)") (class "Default")
      (node (ref "C43") (pin "2") (pinfunction "2_2") (pintype "passive"))
      (node (ref "U7") (pin "32") (pinfunction "VCC_32") (pintype "passive"))
    )
    (net (code "49") (name "Net-(U7-VOUT)") (class "Default")
      (node (ref "C29") (pin "1") (pinfunction "1_1") (pintype "passive"))
      (node (ref "C30") (pin "2") (pinfunction "2_2") (pintype "passive"))
      (node (ref "F4") (pin "1") (pinfunction "1_1") (pintype "passive"))
      (node (ref "L2") (pin "2") (pinfunction "2_2") (pintype "passive"))
      (node (ref "R78") (pin "1") (pinfunction "1_1") (pintype "passive"))
      (node (ref "U7") (pin "17") (pinfunction "VOUT_17") (pintype "passive"))
    )
    (net (code "50") (name "Net-(U8-FB)") (class "Default")
      (node (ref "R100") (pin "2") (pinfunction "2_2") (pintype "passive"))
      (node (ref "R90") (pin "2") (pinfunction "2_2") (pintype "passive"))
      (node (ref "R91") (pin "1") (pinfunction "1_1") (pintype "passive"))
      (node (ref "U8") (pin "3") (pinfunction "FB_3") (pintype "passive"))
    )
    (net (code "51") (name "VIN") (class "Default")
      (node (ref "C14") (pin "1") (pinfunction "1_1") (pintype "passive"))
      (node (ref "R138") (pin "1") (pinfunction "1_1") (pintype "passive"))
      (node (ref "U6") (pin "8") (pinfunction "8_8") (pintype "passive"))
    )
    (net (code "52") (name "unconnected-(J4-ID-Pad4)") (class "Default")
      (node (ref "J4") (pin "4") (pinfunction "ID_4") (pintype "passive"))
    )
    (net (code "53") (name "unconnected-(U7-DM1-Pad5)") (class "Default")
      (node (ref "U7") (pin "5") (pinfunction "DM1_5") (pintype "passive"))
    )
    (net (code "54") (name "unconnected-(U7-DM2-Pad3)") (class "Default")
      (node (ref "U7") (pin "3") (pinfunction "DM2_3") (pintype "passive"))
    )
    (net (code "55") (name "unconnected-(U7-DP1-Pad4)") (class "Default")
      (node (ref "U7") (pin "4") (pinfunction "DP1_4") (pintype "passive"))
    )
    (net (code "56") (name "unconnected-(U7-DP2-Pad2)") (class "Default")
      (node (ref "U7") (pin "2") (pinfunction "DP2_2") (pintype "passive"))
    )
  )
)
